# Circuito_Alarma.net
KiCad netlist of a schematic drawn in EAGLE
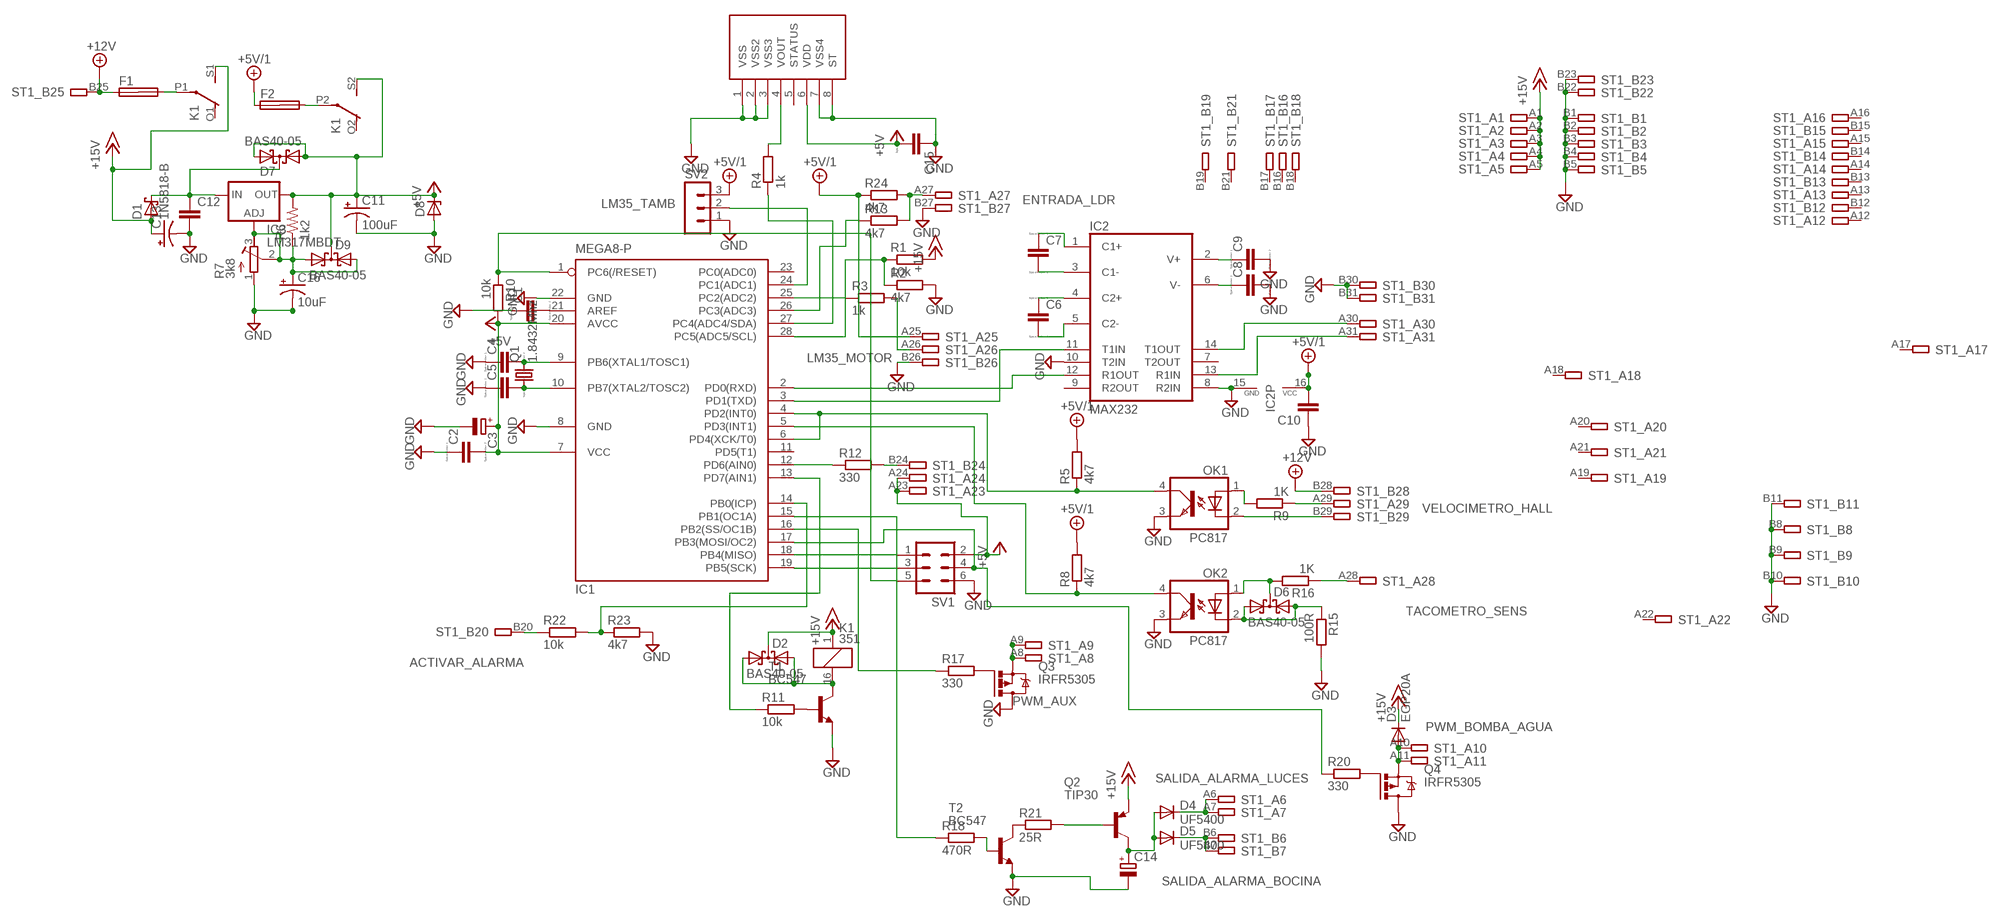
[diagram p0: schematic, sheet 1]

(export (version "E")
  (design (tool "Eeschema 10.0.6"))
  (components
    (comp (ref "C1")
      (value "CC1206")
      (footprint "eagle-import:C1206")
      (libsource (lib "eagle-import") (part "CC1206"))
    )
    (comp (ref "C2")
      (value "CC1206")
      (footprint "eagle-import:C1206")
      (libsource (lib "eagle-import") (part "CC1206"))
    )
    (comp (ref "C3")
      (value "CPOL-EUE2.5-5")
      (footprint "eagle-import:E2,5-5")
      (libsource (lib "eagle-import") (part "CPOL-EUE2.5-5"))
    )
    (comp (ref "C4")
      (value "CC1206")
      (footprint "eagle-import:C1206")
      (libsource (lib "eagle-import") (part "CC1206"))
    )
    (comp (ref "C5")
      (value "CC1206")
      (footprint "eagle-import:C1206")
      (libsource (lib "eagle-import") (part "CC1206"))
    )
    (comp (ref "C6")
      (value "CC1206")
      (footprint "eagle-import:C1206")
      (libsource (lib "eagle-import") (part "CC1206"))
    )
    (comp (ref "C7")
      (value "CC1206")
      (footprint "eagle-import:C1206")
      (libsource (lib "eagle-import") (part "CC1206"))
    )
    (comp (ref "C8")
      (value "CC1206")
      (footprint "eagle-import:C1206")
      (libsource (lib "eagle-import") (part "CC1206"))
    )
    (comp (ref "C9")
      (value "CC1206")
      (footprint "eagle-import:C1206")
      (libsource (lib "eagle-import") (part "CC1206"))
    )
    (comp (ref "C10")
      (value "C-EU050-024X044")
      (footprint "eagle-import:C050-024X044")
      (libsource (lib "eagle-import") (part "C-EU050-024X044"))
    )
    (comp (ref "C11")
      (value "100uF")
      (footprint "eagle-import:E2,5-5")
      (libsource (lib "eagle-import") (part "CPOL-USE2.5-5"))
    )
    (comp (ref "C12")
      (value "C-EU050-024X044")
      (footprint "eagle-import:C050-024X044")
      (libsource (lib "eagle-import") (part "C-EU050-024X044"))
    )
    (comp (ref "C13")
      (value "CPOL-USE2.5-5")
      (footprint "eagle-import:E2,5-5")
      (libsource (lib "eagle-import") (part "CPOL-USE2.5-5"))
    )
    (comp (ref "C14")
      (value "CPOL-EUE2.5-5")
      (footprint "eagle-import:E2,5-5")
      (libsource (lib "eagle-import") (part "CPOL-EUE2.5-5"))
    )
    (comp (ref "C15")
      (value "CC1206")
      (footprint "eagle-import:C1206")
      (libsource (lib "eagle-import") (part "CC1206"))
    )
    (comp (ref "C16")
      (value "10uF")
      (footprint "eagle-import:E2,5-5")
      (libsource (lib "eagle-import") (part "CPOL-USE2.5-5"))
    )
    (comp (ref "D1")
      (value "1N5818-B")
      (footprint "eagle-import:DO41-7.6")
      (libsource (lib "eagle-import") (part "1N5818-B"))
    )
    (comp (ref "D2")
      (value "BAS40-05")
      (footprint "eagle-import:SOT23")
      (libsource (lib "eagle-import") (part "BAS40-05"))
    )
    (comp (ref "D3")
      (value "EGP20A")
      (footprint "eagle-import:DO15-12")
      (libsource (lib "eagle-import") (part "EGP20A"))
    )
    (comp (ref "D4")
      (value "UF5400")
      (footprint "eagle-import:DO201-15")
      (libsource (lib "eagle-import") (part "UF5400"))
    )
    (comp (ref "D5")
      (value "UF5400")
      (footprint "eagle-import:DO201-15")
      (libsource (lib "eagle-import") (part "UF5400"))
    )
    (comp (ref "D6")
      (value "BAS40-05")
      (footprint "eagle-import:SOT23")
      (libsource (lib "eagle-import") (part "BAS40-05"))
    )
    (comp (ref "D7")
      (value "BAS40-05")
      (footprint "eagle-import:SOT23")
      (libsource (lib "eagle-import") (part "BAS40-05"))
    )
    (comp (ref "D8")
      (value "ZENER-DIODEZD-5")
      (footprint "eagle-import:ZDIO-5")
      (libsource (lib "eagle-import") (part "ZENER-DIODEZD-5"))
    )
    (comp (ref "D9")
      (value "BAS40-05")
      (footprint "eagle-import:SOT23")
      (libsource (lib "eagle-import") (part "BAS40-05"))
    )
    (comp (ref "F1")
      (value "SHK20L")
      (footprint "eagle-import:SHK20L")
      (libsource (lib "eagle-import") (part "SHK20L"))
    )
    (comp (ref "F2")
      (value "SHK20L")
      (footprint "eagle-import:SHK20L")
      (libsource (lib "eagle-import") (part "SHK20L"))
    )
    (comp (ref "IC1")
      (value "MEGA8-P")
      (footprint "eagle-import:DIL28-3")
      (libsource (lib "eagle-import") (part "MEGA8-P"))
    )
    (comp (ref "IC2")
      (value "MAX232")
      (footprint "eagle-import:DIL16")
      (fields (field (name "MF") "MAXIM") (field (name "MPN") "MAX232ACPE+"))
      (libsource (lib "eagle-import") (part "MAX232"))
    )
    (comp (ref "IC3")
      (value "LM317MBDT")
      (footprint "eagle-import:DPACK")
      (libsource (lib "eagle-import") (part "LM317?MBDT"))
    )
    (comp (ref "K1")
      (value "351")
      (footprint "eagle-import:351")
      (libsource (lib "eagle-import") (part "351"))
    )
    (comp (ref "OK1")
      (value "PC817")
      (footprint "eagle-import:DIL04")
      (fields (field (name "MPN") "PC817X4J000F"))
      (libsource (lib "eagle-import") (part "PC817"))
    )
    (comp (ref "OK2")
      (value "PC817")
      (footprint "eagle-import:DIL04")
      (fields (field (name "MPN") "PC817X4J000F"))
      (libsource (lib "eagle-import") (part "PC817"))
    )
    (comp (ref "Q1")
      (value "1.8432Mhz")
      (footprint "eagle-import:TC26H")
      (libsource (lib "eagle-import") (part "CRYSTALTC26H"))
    )
    (comp (ref "Q2")
      (value "TIP30")
      (footprint "eagle-import:TO220")
      (libsource (lib "eagle-import") (part "TIP30"))
    )
    (comp (ref "Q3")
      (value "IRFR5305")
      (footprint "eagle-import:D-PAK_TO252AA")
      (libsource (lib "eagle-import") (part "IRF?5305R"))
    )
    (comp (ref "Q4")
      (value "IRFR5305")
      (footprint "eagle-import:D-PAK_TO252AA")
      (libsource (lib "eagle-import") (part "IRF?5305R"))
    )
    (comp (ref "R1")
      (value "10k")
      (footprint "eagle-import:0204_5")
      (libsource (lib "eagle-import") (part "R-EU_0204/5"))
    )
    (comp (ref "R2")
      (value "4k7")
      (footprint "eagle-import:0204_5")
      (libsource (lib "eagle-import") (part "R-EU_0204/5"))
    )
    (comp (ref "R3")
      (value "1k")
      (footprint "eagle-import:0204_5")
      (libsource (lib "eagle-import") (part "R-EU_0204/5"))
    )
    (comp (ref "R4")
      (value "1k")
      (footprint "eagle-import:0204_5")
      (libsource (lib "eagle-import") (part "R-EU_0204/5"))
    )
    (comp (ref "R5")
      (value "4k7")
      (footprint "eagle-import:0204_5")
      (libsource (lib "eagle-import") (part "R-EU_0204/5"))
    )
    (comp (ref "R6")
      (value "1k2")
      (footprint "eagle-import:M1206")
      (libsource (lib "eagle-import") (part "R-US_M1206"))
    )
    (comp (ref "R7")
      (value "3k8")
      (footprint "eagle-import:RTRIM64W")
      (libsource (lib "eagle-import") (part "R-TRIMM64W"))
    )
    (comp (ref "R8")
      (value "4k7")
      (footprint "eagle-import:0204_5")
      (libsource (lib "eagle-import") (part "R-EU_0204/5"))
    )
    (comp (ref "R9")
      (value "1K")
      (footprint "eagle-import:0204_5")
      (libsource (lib "eagle-import") (part "R-EU_0204/5"))
    )
    (comp (ref "R10")
      (value "10k")
      (footprint "eagle-import:0204_5")
      (libsource (lib "eagle-import") (part "R-EU_0204/5"))
    )
    (comp (ref "R11")
      (value "10k")
      (footprint "eagle-import:0204_5")
      (libsource (lib "eagle-import") (part "R-EU_0204/5"))
    )
    (comp (ref "R12")
      (value "330")
      (footprint "eagle-import:0204_5")
      (libsource (lib "eagle-import") (part "R-EU_0204/5"))
    )
    (comp (ref "R13")
      (value "4k7")
      (footprint "eagle-import:0204_5")
      (libsource (lib "eagle-import") (part "R-EU_0204/5"))
    )
    (comp (ref "R15")
      (value "100R")
      (footprint "eagle-import:0204_5")
      (libsource (lib "eagle-import") (part "R-EU_0204/5"))
    )
    (comp (ref "R16")
      (value "1K")
      (footprint "eagle-import:0204_5")
      (libsource (lib "eagle-import") (part "R-EU_0204/5"))
    )
    (comp (ref "R17")
      (value "330")
      (footprint "eagle-import:0204_5")
      (libsource (lib "eagle-import") (part "R-EU_0204/5"))
    )
    (comp (ref "R18")
      (value "470R")
      (footprint "eagle-import:0204_5")
      (libsource (lib "eagle-import") (part "R-EU_0204/5"))
    )
    (comp (ref "R20")
      (value "330")
      (footprint "eagle-import:0204_5")
      (libsource (lib "eagle-import") (part "R-EU_0204/5"))
    )
    (comp (ref "R21")
      (value "25R")
      (footprint "eagle-import:0411_12")
      (libsource (lib "eagle-import") (part "R-EU_0411/12"))
    )
    (comp (ref "R22")
      (value "10k")
      (footprint "eagle-import:0204_5")
      (libsource (lib "eagle-import") (part "R-EU_0204/5"))
    )
    (comp (ref "R23")
      (value "4k7")
      (footprint "eagle-import:0204_5")
      (libsource (lib "eagle-import") (part "R-EU_0204/5"))
    )
    (comp (ref "R24")
      (value "4k7")
      (footprint "eagle-import:0204_5")
      (libsource (lib "eagle-import") (part "R-EU_0204/5"))
    )
    (comp (ref "ST1")
      (value "IBM8BIT")
      (footprint "eagle-import:IBM8BIT")
      (libsource (lib "eagle-import") (part "IBM8BIT"))
    )
    (comp (ref "SV1")
      (value "MA03-2")
      (footprint "eagle-import:MA03-2")
      (libsource (lib "eagle-import") (part "MA03-2"))
    )
    (comp (ref "SV2")
      (value "MA03-1")
      (footprint "eagle-import:MA03-1")
      (libsource (lib "eagle-import") (part "MA03-1"))
    )
    (comp (ref "T1")
      (value "BC547")
      (footprint "eagle-import:TO92")
      (libsource (lib "eagle-import") (part "BC547"))
    )
    (comp (ref "T2")
      (value "BC547")
      (footprint "eagle-import:TO92")
      (libsource (lib "eagle-import") (part "BC547"))
    )
    (comp (ref "U$1")
      (value "MMA1260")
      (footprint "eagle-import:N5")
      (libsource (lib "eagle-import") (part "MMA1260"))
    )
  )
  (nets
    (net (code "1") (name "+5V") (class "Default")
      (node (ref "C11") (pin "+") (pinfunction "+_+") (pintype "passive"))
      (node (ref "C15") (pin "2") (pinfunction "2_2") (pintype "passive"))
      (node (ref "C2") (pin "2") (pinfunction "2_2") (pintype "passive"))
      (node (ref "C3") (pin "+") (pinfunction "+_+") (pintype "passive"))
      (node (ref "D7") (pin "1") (pinfunction "A1_1") (pintype "passive"))
      (node (ref "D7") (pin "2") (pinfunction "A2_2") (pintype "passive"))
      (node (ref "D8") (pin "C") (pinfunction "C_C") (pintype "passive"))
      (node (ref "D9") (pin "3") (pinfunction "C_3") (pintype "passive"))
      (node (ref "IC1") (pin "20") (pinfunction "AVCC_20") (pintype "power_in"))
      (node (ref "IC1") (pin "7") (pinfunction "VCC_7") (pintype "power_in"))
      (node (ref "IC3") (pin "4") (pinfunction "OUT_4") (pintype "passive"))
      (node (ref "K1") (pin "S2") (pinfunction "S_S2") (pintype "passive"))
      (node (ref "R10") (pin "2") (pinfunction "2_2") (pintype "passive"))
      (node (ref "R6") (pin "2") (pinfunction "2_2") (pintype "passive"))
      (node (ref "ST1") (pin "A23") (pinfunction "P_A23") (pintype "bidirectional"))
      (node (ref "ST1") (pin "A24") (pinfunction "P_A24") (pintype "bidirectional"))
      (node (ref "SV1") (pin "2") (pinfunction "2_2") (pintype "passive"))
      (node (ref "U$1") (pin "6") (pinfunction "VDD_6") (pintype "bidirectional"))
    )
    (net (code "2") (name "+5V{slash}1") (class "Default")
      (node (ref "C10") (pin "2") (pinfunction "2_2") (pintype "passive"))
      (node (ref "F2") (pin "1A") (pinfunction "1A_1A") (pintype "passive"))
      (node (ref "IC2") (pin "16") (pinfunction "VCC_16") (pintype "power_in"))
      (node (ref "R24") (pin "1") (pinfunction "1_1") (pintype "passive"))
      (node (ref "R5") (pin "2") (pinfunction "2_2") (pintype "passive"))
      (node (ref "R8") (pin "2") (pinfunction "2_2") (pintype "passive"))
      (node (ref "ST1") (pin "A25") (pinfunction "P_A25") (pintype "bidirectional"))
      (node (ref "SV2") (pin "3") (pinfunction "3_3") (pintype "passive"))
    )
    (net (code "3") (name "+12V") (class "Default")
      (node (ref "F1") (pin "1A") (pinfunction "1A_1A") (pintype "passive"))
      (node (ref "ST1") (pin "B25") (pinfunction "P_B25") (pintype "bidirectional"))
      (node (ref "ST1") (pin "B28") (pinfunction "P_B28") (pintype "bidirectional"))
    )
    (net (code "4") (name "+15V") (class "Default")
      (node (ref "C13") (pin "+") (pinfunction "+_+") (pintype "passive"))
      (node (ref "D1") (pin "A") (pinfunction "A_A") (pintype "passive"))
      (node (ref "D2") (pin "3") (pinfunction "C_3") (pintype "passive"))
      (node (ref "D3") (pin "C") (pinfunction "C_C") (pintype "passive"))
      (node (ref "K1") (pin "1") (pinfunction "1_1") (pintype "passive"))
      (node (ref "K1") (pin "S1") (pinfunction "S_S1") (pintype "passive"))
      (node (ref "Q2") (pin "3") (pinfunction "E_3") (pintype "passive"))
      (node (ref "R1") (pin "2") (pinfunction "2_2") (pintype "passive"))
      (node (ref "ST1") (pin "A1") (pinfunction "P_A1") (pintype "bidirectional"))
      (node (ref "ST1") (pin "A2") (pinfunction "P_A2") (pintype "bidirectional"))
      (node (ref "ST1") (pin "A3") (pinfunction "P_A3") (pintype "bidirectional"))
      (node (ref "ST1") (pin "A4") (pinfunction "P_A4") (pintype "bidirectional"))
      (node (ref "ST1") (pin "A5") (pinfunction "P_A5") (pintype "bidirectional"))
    )
    (net (code "5") (name "/ACTIVAR_ALARMA") (class "Default")
      (node (ref "R22") (pin "1") (pinfunction "1_1") (pintype "passive"))
      (node (ref "ST1") (pin "B20") (pinfunction "P_B20") (pintype "bidirectional"))
    )
    (net (code "6") (name "/ENTRADA_LDR") (class "Default")
      (node (ref "R13") (pin "2") (pinfunction "2_2") (pintype "passive"))
      (node (ref "R24") (pin "2") (pinfunction "2_2") (pintype "passive"))
      (node (ref "ST1") (pin "A27") (pinfunction "P_A27") (pintype "bidirectional"))
    )
    (net (code "7") (name "/LM35_MOTOR") (class "Default")
      (node (ref "R3") (pin "2") (pinfunction "2_2") (pintype "passive"))
      (node (ref "ST1") (pin "A26") (pinfunction "P_A26") (pintype "bidirectional"))
    )
    (net (code "8") (name "/LM35_TAMB") (class "Default")
      (node (ref "IC1") (pin "24") (pinfunction "PC1(ADC1)_24") (pintype "bidirectional"))
      (node (ref "SV2") (pin "2") (pinfunction "2_2") (pintype "passive"))
    )
    (net (code "9") (name "/PWM_AUX") (class "Default")
      (node (ref "Q3") (pin "3") (pinfunction "S_3") (pintype "passive"))
      (node (ref "ST1") (pin "A8") (pinfunction "P_A8") (pintype "bidirectional"))
      (node (ref "ST1") (pin "A9") (pinfunction "P_A9") (pintype "bidirectional"))
    )
    (net (code "10") (name "/PWM_BOMBA_AGUA") (class "Default")
      (node (ref "D3") (pin "A") (pinfunction "A_A") (pintype "passive"))
      (node (ref "Q4") (pin "3") (pinfunction "S_3") (pintype "passive"))
      (node (ref "ST1") (pin "A10") (pinfunction "P_A10") (pintype "bidirectional"))
      (node (ref "ST1") (pin "A11") (pinfunction "P_A11") (pintype "bidirectional"))
    )
    (net (code "11") (name "/SALIDA_ALARMA_BOCINA") (class "Default")
      (node (ref "D5") (pin "C") (pinfunction "C_C") (pintype "passive"))
      (node (ref "ST1") (pin "B6") (pinfunction "P_B6") (pintype "bidirectional"))
      (node (ref "ST1") (pin "B7") (pinfunction "P_B7") (pintype "bidirectional"))
    )
    (net (code "12") (name "/SALIDA_ALARMA_LUCES") (class "Default")
      (node (ref "D4") (pin "C") (pinfunction "C_C") (pintype "passive"))
      (node (ref "ST1") (pin "A6") (pinfunction "P_A6") (pintype "bidirectional"))
      (node (ref "ST1") (pin "A7") (pinfunction "P_A7") (pintype "bidirectional"))
    )
    (net (code "13") (name "/TACOMETRO_SENS") (class "Default")
      (node (ref "D6") (pin "1") (pinfunction "A1_1") (pintype "passive"))
      (node (ref "D6") (pin "2") (pinfunction "A2_2") (pintype "passive"))
      (node (ref "OK2") (pin "2") (pinfunction "C_2") (pintype "passive"))
      (node (ref "R15") (pin "1") (pinfunction "1_1") (pintype "passive"))
    )
    (net (code "14") (name "/VELOCIMETRO_HALL") (class "Default")
      (node (ref "OK1") (pin "2") (pinfunction "C_2") (pintype "passive"))
      (node (ref "ST1") (pin "B29") (pinfunction "P_B29") (pintype "bidirectional"))
    )
    (net (code "15") (name "GND") (class "Default")
      (node (ref "C1") (pin "1") (pinfunction "1_1") (pintype "passive"))
      (node (ref "C10") (pin "1") (pinfunction "1_1") (pintype "passive"))
      (node (ref "C11") (pin "-") (pinfunction "-_-") (pintype "passive"))
      (node (ref "C12") (pin "2") (pinfunction "2_2") (pintype "passive"))
      (node (ref "C13") (pin "-") (pinfunction "-_-") (pintype "passive"))
      (node (ref "C14") (pin "-") (pinfunction "-_-") (pintype "passive"))
      (node (ref "C15") (pin "1") (pinfunction "1_1") (pintype "passive"))
      (node (ref "C16") (pin "-") (pinfunction "-_-") (pintype "passive"))
      (node (ref "C2") (pin "1") (pinfunction "1_1") (pintype "passive"))
      (node (ref "C3") (pin "-") (pinfunction "-_-") (pintype "passive"))
      (node (ref "C4") (pin "1") (pinfunction "1_1") (pintype "passive"))
      (node (ref "C5") (pin "1") (pinfunction "1_1") (pintype "passive"))
      (node (ref "C8") (pin "2") (pinfunction "2_2") (pintype "passive"))
      (node (ref "C9") (pin "2") (pinfunction "2_2") (pintype "passive"))
      (node (ref "D8") (pin "A") (pinfunction "A_A") (pintype "passive"))
      (node (ref "IC1") (pin "22") (pinfunction "GND_22") (pintype "power_in"))
      (node (ref "IC1") (pin "8") (pinfunction "GND_8") (pintype "power_in"))
      (node (ref "IC2") (pin "10") (pinfunction "T2IN_10") (pintype "input"))
      (node (ref "IC2") (pin "15") (pinfunction "GND_15") (pintype "power_in"))
      (node (ref "IC2") (pin "8") (pinfunction "R2IN_8") (pintype "input"))
      (node (ref "OK1") (pin "3") (pinfunction "EMIT_3") (pintype "passive"))
      (node (ref "OK2") (pin "3") (pinfunction "EMIT_3") (pintype "passive"))
      (node (ref "Q3") (pin "4") (pinfunction "D_4") (pintype "passive"))
      (node (ref "Q4") (pin "4") (pinfunction "D_4") (pintype "passive"))
      (node (ref "R15") (pin "2") (pinfunction "2_2") (pintype "passive"))
      (node (ref "R2") (pin "2") (pinfunction "2_2") (pintype "passive"))
      (node (ref "R23") (pin "2") (pinfunction "2_2") (pintype "passive"))
      (node (ref "R7") (pin "1") (pinfunction "E_1") (pintype "passive"))
      (node (ref "ST1") (pin "B1") (pinfunction "P_B1") (pintype "bidirectional"))
      (node (ref "ST1") (pin "B10") (pinfunction "P_B10") (pintype "bidirectional"))
      (node (ref "ST1") (pin "B11") (pinfunction "P_B11") (pintype "bidirectional"))
      (node (ref "ST1") (pin "B2") (pinfunction "P_B2") (pintype "bidirectional"))
      (node (ref "ST1") (pin "B22") (pinfunction "P_B22") (pintype "bidirectional"))
      (node (ref "ST1") (pin "B23") (pinfunction "P_B23") (pintype "bidirectional"))
      (node (ref "ST1") (pin "B26") (pinfunction "P_B26") (pintype "bidirectional"))
      (node (ref "ST1") (pin "B27") (pinfunction "P_B27") (pintype "bidirectional"))
      (node (ref "ST1") (pin "B3") (pinfunction "P_B3") (pintype "bidirectional"))
      (node (ref "ST1") (pin "B30") (pinfunction "P_B30") (pintype "bidirectional"))
      (node (ref "ST1") (pin "B31") (pinfunction "P_B31") (pintype "bidirectional"))
      (node (ref "ST1") (pin "B4") (pinfunction "P_B4") (pintype "bidirectional"))
      (node (ref "ST1") (pin "B5") (pinfunction "P_B5") (pintype "bidirectional"))
      (node (ref "ST1") (pin "B8") (pinfunction "P_B8") (pintype "bidirectional"))
      (node (ref "ST1") (pin "B9") (pinfunction "P_B9") (pintype "bidirectional"))
      (node (ref "SV1") (pin "6") (pinfunction "6_6") (pintype "passive"))
      (node (ref "SV2") (pin "1") (pinfunction "1_1") (pintype "passive"))
      (node (ref "T1") (pin "1") (pinfunction "E_1") (pintype "passive"))
      (node (ref "T2") (pin "1") (pinfunction "E_1") (pintype "passive"))
      (node (ref "U$1") (pin "1") (pinfunction "VSS_1") (pintype "bidirectional"))
      (node (ref "U$1") (pin "2") (pinfunction "VSS2_2") (pintype "bidirectional"))
      (node (ref "U$1") (pin "3") (pinfunction "VSS3_3") (pintype "bidirectional"))
      (node (ref "U$1") (pin "7") (pinfunction "VSS4_7") (pintype "bidirectional"))
      (node (ref "U$1") (pin "8") (pinfunction "ST_8") (pintype "bidirectional"))
    )
    (net (code "16") (name "Net-(D2-A1)") (class "Default")
      (node (ref "D2") (pin "1") (pinfunction "A1_1") (pintype "passive"))
      (node (ref "D2") (pin "2") (pinfunction "A2_2") (pintype "passive"))
      (node (ref "K1") (pin "16") (pinfunction "2_16") (pintype "passive"))
      (node (ref "T1") (pin "3") (pinfunction "C_3") (pintype "passive"))
    )
    (net (code "17") (name "Net-(D6-C)") (class "Default")
      (node (ref "D6") (pin "3") (pinfunction "C_3") (pintype "passive"))
      (node (ref "OK2") (pin "1") (pinfunction "A_1") (pintype "passive"))
      (node (ref "R16") (pin "2") (pinfunction "2_2") (pintype "passive"))
    )
    (net (code "18") (name "Net-(D7-C)") (class "Default")
      (node (ref "C12") (pin "1") (pinfunction "1_1") (pintype "passive"))
      (node (ref "D1") (pin "C") (pinfunction "C_C") (pintype "passive"))
      (node (ref "D7") (pin "3") (pinfunction "C_3") (pintype "passive"))
      (node (ref "IC3") (pin "3") (pinfunction "IN_3") (pintype "input"))
    )
    (net (code "19") (name "Net-(D9-A1)") (class "Default")
      (node (ref "C16") (pin "+") (pinfunction "+_+") (pintype "passive"))
      (node (ref "D9") (pin "1") (pinfunction "A1_1") (pintype "passive"))
      (node (ref "D9") (pin "2") (pinfunction "A2_2") (pintype "passive"))
      (node (ref "IC3") (pin "1") (pinfunction "ADJ_1") (pintype "input"))
      (node (ref "R6") (pin "1") (pinfunction "1_1") (pintype "passive"))
      (node (ref "R7") (pin "2") (pinfunction "S_2") (pintype "passive"))
      (node (ref "R7") (pin "3") (pinfunction "A_3") (pintype "passive"))
    )
    (net (code "20") (name "Net-(IC1-AREF)") (class "Default")
      (node (ref "C1") (pin "2") (pinfunction "2_2") (pintype "passive"))
      (node (ref "IC1") (pin "21") (pinfunction "AREF_21") (pintype "passive"))
    )
    (net (code "21") (name "Net-(IC1-PB0(ICP))") (class "Default")
      (node (ref "IC1") (pin "14") (pinfunction "PB0(ICP)_14") (pintype "bidirectional"))
      (node (ref "R22") (pin "2") (pinfunction "2_2") (pintype "passive"))
      (node (ref "R23") (pin "1") (pinfunction "1_1") (pintype "passive"))
    )
    (net (code "22") (name "Net-(IC1-PB1(OC1A))") (class "Default")
      (node (ref "IC1") (pin "15") (pinfunction "PB1(OC1A)_15") (pintype "bidirectional"))
      (node (ref "R18") (pin "1") (pinfunction "1_1") (pintype "passive"))
    )
    (net (code "23") (name "Net-(IC1-PB2(SS{slash}OC1B))") (class "Default")
      (node (ref "IC1") (pin "16") (pinfunction "PB2(SS/OC1B)_16") (pintype "bidirectional"))
      (node (ref "R17") (pin "1") (pinfunction "1_1") (pintype "passive"))
    )
    (net (code "24") (name "Net-(IC1-PB3(MOSI{slash}OC2))") (class "Default")
      (node (ref "IC1") (pin "17") (pinfunction "PB3(MOSI/OC2)_17") (pintype "bidirectional"))
      (node (ref "R20") (pin "1") (pinfunction "1_1") (pintype "passive"))
      (node (ref "SV1") (pin "4") (pinfunction "4_4") (pintype "passive"))
    )
    (net (code "25") (name "Net-(IC1-PB4(MISO))") (class "Default")
      (node (ref "IC1") (pin "18") (pinfunction "PB4(MISO)_18") (pintype "bidirectional"))
      (node (ref "SV1") (pin "1") (pinfunction "1_1") (pintype "passive"))
    )
    (net (code "26") (name "Net-(IC1-PB5(SCK))") (class "Default")
      (node (ref "IC1") (pin "19") (pinfunction "PB5(SCK)_19") (pintype "bidirectional"))
      (node (ref "SV1") (pin "3") (pinfunction "3_3") (pintype "passive"))
    )
    (net (code "27") (name "Net-(IC1-PB6(XTAL1{slash}TOSC1))") (class "Default")
      (node (ref "C4") (pin "2") (pinfunction "2_2") (pintype "passive"))
      (node (ref "IC1") (pin "9") (pinfunction "PB6(XTAL1/TOSC1)_9") (pintype "bidirectional"))
      (node (ref "Q1") (pin "2") (pinfunction "2_2") (pintype "passive"))
    )
    (net (code "28") (name "Net-(IC1-PB7(XTAL2{slash}TOSC2))") (class "Default")
      (node (ref "C5") (pin "2") (pinfunction "2_2") (pintype "passive"))
      (node (ref "IC1") (pin "10") (pinfunction "PB7(XTAL2/TOSC2)_10") (pintype "bidirectional"))
      (node (ref "Q1") (pin "1") (pinfunction "1_1") (pintype "passive"))
    )
    (net (code "29") (name "Net-(IC1-PC2(ADC2))") (class "Default")
      (node (ref "IC1") (pin "25") (pinfunction "PC2(ADC2)_25") (pintype "bidirectional"))
      (node (ref "R3") (pin "1") (pinfunction "1_1") (pintype "passive"))
    )
    (net (code "30") (name "Net-(IC1-PC3(ADC3))") (class "Default")
      (node (ref "IC1") (pin "26") (pinfunction "PC3(ADC3)_26") (pintype "bidirectional"))
      (node (ref "R13") (pin "1") (pinfunction "1_1") (pintype "passive"))
    )
    (net (code "31") (name "Net-(IC1-PC4(ADC4{slash}SDA))") (class "Default")
      (node (ref "IC1") (pin "27") (pinfunction "PC4(ADC4/SDA)_27") (pintype "bidirectional"))
      (node (ref "R4") (pin "1") (pinfunction "1_1") (pintype "passive"))
    )
    (net (code "32") (name "Net-(IC1-PC5(ADC5{slash}SCL))") (class "Default")
      (node (ref "IC1") (pin "28") (pinfunction "PC5(ADC5/SCL)_28") (pintype "bidirectional"))
      (node (ref "R1") (pin "1") (pinfunction "1_1") (pintype "passive"))
      (node (ref "R2") (pin "1") (pinfunction "1_1") (pintype "passive"))
    )
    (net (code "33") (name "Net-(IC1-PC6({slash}RESET))") (class "Default")
      (node (ref "IC1") (pin "1") (pinfunction "PC6(/RESET)_1") (pintype "bidirectional"))
      (node (ref "R10") (pin "1") (pinfunction "1_1") (pintype "passive"))
      (node (ref "SV1") (pin "5") (pinfunction "5_5") (pintype "passive"))
    )
    (net (code "34") (name "Net-(IC1-PD0(RXD))") (class "Default")
      (node (ref "IC1") (pin "2") (pinfunction "PD0(RXD)_2") (pintype "bidirectional"))
      (node (ref "IC2") (pin "12") (pinfunction "R1OUT_12") (pintype "output"))
    )
    (net (code "35") (name "Net-(IC1-PD1(TXD))") (class "Default")
      (node (ref "IC1") (pin "3") (pinfunction "PD1(TXD)_3") (pintype "bidirectional"))
      (node (ref "IC2") (pin "11") (pinfunction "T1IN_11") (pintype "input"))
    )
    (net (code "36") (name "Net-(IC1-PD2(INT0))") (class "Default")
      (node (ref "IC1") (pin "4") (pinfunction "PD2(INT0)_4") (pintype "bidirectional"))
      (node (ref "IC1") (pin "6") (pinfunction "PD4(XCK/T0)_6") (pintype "bidirectional"))
      (node (ref "OK1") (pin "4") (pinfunction "COL_4") (pintype "passive"))
      (node (ref "R5") (pin "1") (pinfunction "1_1") (pintype "passive"))
    )
    (net (code "37") (name "Net-(IC1-PD3(INT1))") (class "Default")
      (node (ref "IC1") (pin "5") (pinfunction "PD3(INT1)_5") (pintype "bidirectional"))
      (node (ref "OK2") (pin "4") (pinfunction "COL_4") (pintype "passive"))
      (node (ref "R8") (pin "1") (pinfunction "1_1") (pintype "passive"))
    )
    (net (code "38") (name "Net-(IC1-PD6(AIN0))") (class "Default")
      (node (ref "IC1") (pin "12") (pinfunction "PD6(AIN0)_12") (pintype "bidirectional"))
      (node (ref "R12") (pin "1") (pinfunction "1_1") (pintype "passive"))
    )
    (net (code "39") (name "Net-(IC1-PD7(AIN1))") (class "Default")
      (node (ref "IC1") (pin "13") (pinfunction "PD7(AIN1)_13") (pintype "bidirectional"))
      (node (ref "R11") (pin "1") (pinfunction "1_1") (pintype "passive"))
    )
    (net (code "40") (name "Net-(IC2A-C1+)") (class "Default")
      (node (ref "C7") (pin "1") (pinfunction "1_1") (pintype "passive"))
      (node (ref "IC2") (pin "1") (pinfunction "C1+_1") (pintype "bidirectional"))
    )
    (net (code "41") (name "Net-(IC2A-C1-)") (class "Default")
      (node (ref "C7") (pin "2") (pinfunction "2_2") (pintype "passive"))
      (node (ref "IC2") (pin "3") (pinfunction "C1-_3") (pintype "bidirectional"))
    )
    (net (code "42") (name "Net-(IC2A-C2+)") (class "Default")
      (node (ref "C6") (pin "1") (pinfunction "1_1") (pintype "passive"))
      (node (ref "IC2") (pin "4") (pinfunction "C2+_4") (pintype "bidirectional"))
    )
    (net (code "43") (name "Net-(IC2A-C2-)") (class "Default")
      (node (ref "C6") (pin "2") (pinfunction "2_2") (pintype "passive"))
      (node (ref "IC2") (pin "5") (pinfunction "C2-_5") (pintype "bidirectional"))
    )
    (net (code "44") (name "Net-(IC2A-R1IN)") (class "Default")
      (node (ref "IC2") (pin "13") (pinfunction "R1IN_13") (pintype "input"))
      (node (ref "ST1") (pin "A31") (pinfunction "P_A31") (pintype "bidirectional"))
    )
    (net (code "45") (name "Net-(IC2A-T1OUT)") (class "Default")
      (node (ref "IC2") (pin "14") (pinfunction "T1OUT_14") (pintype "output"))
      (node (ref "ST1") (pin "A30") (pinfunction "P_A30") (pintype "bidirectional"))
    )
    (net (code "46") (name "Net-(IC2A-V+)") (class "Default")
      (node (ref "C9") (pin "1") (pinfunction "1_1") (pintype "passive"))
      (node (ref "IC2") (pin "2") (pinfunction "V+_2") (pintype "bidirectional"))
    )
    (net (code "47") (name "Net-(IC2A-V-)") (class "Default")
      (node (ref "C8") (pin "1") (pinfunction "1_1") (pintype "passive"))
      (node (ref "IC2") (pin "6") (pinfunction "V-_6") (pintype "bidirectional"))
    )
    (net (code "48") (name "Net-(K1B-P)") (class "Default")
      (node (ref "F1") (pin "2A") (pinfunction "2A_2A") (pintype "passive"))
      (node (ref "K1") (pin "P1") (pinfunction "P_P1") (pintype "passive"))
    )
    (net (code "49") (name "Net-(K1C-P)") (class "Default")
      (node (ref "F2") (pin "2A") (pinfunction "2A_2A") (pintype "passive"))
      (node (ref "K1") (pin "P2") (pinfunction "P_P2") (pintype "passive"))
    )
    (net (code "50") (name "Net-(OK1-A)") (class "Default")
      (node (ref "OK1") (pin "1") (pinfunction "A_1") (pintype "passive"))
      (node (ref "R9") (pin "2") (pinfunction "2_2") (pintype "passive"))
    )
    (net (code "51") (name "Net-(Q2-B)") (class "Default")
      (node (ref "Q2") (pin "1") (pinfunction "B_1") (pintype "passive"))
      (node (ref "R21") (pin "2") (pinfunction "2_2") (pintype "passive"))
    )
    (net (code "52") (name "Net-(Q2-C)") (class "Default")
      (node (ref "C14") (pin "+") (pinfunction "+_+") (pintype "passive"))
      (node (ref "D4") (pin "A") (pinfunction "A_A") (pintype "passive"))
      (node (ref "D5") (pin "A") (pinfunction "A_A") (pintype "passive"))
      (node (ref "Q2") (pin "2") (pinfunction "C_2") (pintype "passive"))
    )
    (net (code "53") (name "Net-(Q3-G)") (class "Default")
      (node (ref "Q3") (pin "1") (pinfunction "G_1") (pintype "passive"))
      (node (ref "R17") (pin "2") (pinfunction "2_2") (pintype "passive"))
    )
    (net (code "54") (name "Net-(Q4-G)") (class "Default")
      (node (ref "Q4") (pin "1") (pinfunction "G_1") (pintype "passive"))
      (node (ref "R20") (pin "2") (pinfunction "2_2") (pintype "passive"))
    )
    (net (code "55") (name "Net-(ST1AV-P)") (class "Default")
      (node (ref "R12") (pin "2") (pinfunction "2_2") (pintype "passive"))
      (node (ref "ST1") (pin "B24") (pinfunction "P_B24") (pintype "bidirectional"))
    )
    (net (code "56") (name "Net-(ST1U-P)") (class "Default")
      (node (ref "R16") (pin "1") (pinfunction "1_1") (pintype "passive"))
      (node (ref "ST1") (pin "A28") (pinfunction "P_A28") (pintype "bidirectional"))
    )
    (net (code "57") (name "Net-(ST1V-P)") (class "Default")
      (node (ref "R9") (pin "1") (pinfunction "1_1") (pintype "passive"))
      (node (ref "ST1") (pin "A29") (pinfunction "P_A29") (pintype "bidirectional"))
    )
    (net (code "58") (name "Net-(T1-B)") (class "Default")
      (node (ref "R11") (pin "2") (pinfunction "2_2") (pintype "passive"))
      (node (ref "T1") (pin "2") (pinfunction "B_2") (pintype "passive"))
    )
    (net (code "59") (name "Net-(T2-B)") (class "Default")
      (node (ref "R18") (pin "2") (pinfunction "2_2") (pintype "passive"))
      (node (ref "T2") (pin "2") (pinfunction "B_2") (pintype "passive"))
    )
    (net (code "60") (name "Net-(T2-C)") (class "Default")
      (node (ref "R21") (pin "1") (pinfunction "1_1") (pintype "passive"))
      (node (ref "T2") (pin "3") (pinfunction "C_3") (pintype "passive"))
    )
    (net (code "61") (name "Net-(U$1-VOUT)") (class "Default")
      (node (ref "R4") (pin "2") (pinfunction "2_2") (pintype "passive"))
      (node (ref "U$1") (pin "4") (pinfunction "VOUT_4") (pintype "bidirectional"))
    )
    (net (code "62") (name "unconnected-(F1-Pad1B)") (class "Default")
      (node (ref "F1") (pin "1B") (pinfunction "1B_1B") (pintype "passive"))
    )
    (net (code "63") (name "unconnected-(F1-Pad2B)") (class "Default")
      (node (ref "F1") (pin "2B") (pinfunction "2B_2B") (pintype "passive"))
    )
    (net (code "64") (name "unconnected-(F2-Pad1B)") (class "Default")
      (node (ref "F2") (pin "1B") (pinfunction "1B_1B") (pintype "passive"))
    )
    (net (code "65") (name "unconnected-(F2-Pad2B)") (class "Default")
      (node (ref "F2") (pin "2B") (pinfunction "2B_2B") (pintype "passive"))
    )
    (net (code "66") (name "unconnected-(IC1-PC0(ADC0)-Pad23)") (class "Default")
      (node (ref "IC1") (pin "23") (pinfunction "PC0(ADC0)_23") (pintype "bidirectional"))
    )
    (net (code "67") (name "unconnected-(IC1-PD5(T1)-Pad11)") (class "Default")
      (node (ref "IC1") (pin "11") (pinfunction "PD5(T1)_11") (pintype "bidirectional"))
    )
    (net (code "68") (name "unconnected-(IC2A-R2OUT-Pad9)") (class "Default")
      (node (ref "IC2") (pin "9") (pinfunction "R2OUT_9") (pintype "output"))
    )
    (net (code "69") (name "unconnected-(IC2A-T2OUT-Pad7)") (class "Default")
      (node (ref "IC2") (pin "7") (pinfunction "T2OUT_7") (pintype "output"))
    )
    (net (code "70") (name "unconnected-(K1B-O-PadO1)") (class "Default")
      (node (ref "K1") (pin "O1") (pinfunction "O_O1") (pintype "passive"))
    )
    (net (code "71") (name "unconnected-(K1C-O-PadO2)") (class "Default")
      (node (ref "K1") (pin "O2") (pinfunction "O_O2") (pintype "passive"))
    )
    (net (code "72") (name "unconnected-(ST1AI-P-PadB12)") (class "Default")
      (node (ref "ST1") (pin "B12") (pinfunction "P_B12") (pintype "bidirectional"))
    )
    (net (code "73") (name "unconnected-(ST1AJ-P-PadB13)") (class "Default")
      (node (ref "ST1") (pin "B13") (pinfunction "P_B13") (pintype "bidirectional"))
    )
    (net (code "74") (name "unconnected-(ST1AK-P-PadB14)") (class "Default")
      (node (ref "ST1") (pin "B14") (pinfunction "P_B14") (pintype "bidirectional"))
    )
    (net (code "75") (name "unconnected-(ST1AL-P-PadB15)") (class "Default")
      (node (ref "ST1") (pin "B15") (pinfunction "P_B15") (pintype "bidirectional"))
    )
    (net (code "76") (name "unconnected-(ST1AM-P-PadB16)") (class "Default")
      (node (ref "ST1") (pin "B16") (pinfunction "P_B16") (pintype "bidirectional"))
    )
    (net (code "77") (name "unconnected-(ST1AN-P-PadB17)") (class "Default")
      (node (ref "ST1") (pin "B17") (pinfunction "P_B17") (pintype "bidirectional"))
    )
    (net (code "78") (name "unconnected-(ST1AO-P-PadB18)") (class "Default")
      (node (ref "ST1") (pin "B18") (pinfunction "P_B18") (pintype "bidirectional"))
    )
    (net (code "79") (name "unconnected-(ST1AP-P-PadB19)") (class "Default")
      (node (ref "ST1") (pin "B19") (pinfunction "P_B19") (pintype "bidirectional"))
    )
    (net (code "80") (name "unconnected-(ST1AS-P-PadB21)") (class "Default")
      (node (ref "ST1") (pin "B21") (pinfunction "P_B21") (pintype "bidirectional"))
    )
    (net (code "81") (name "unconnected-(ST1D-P-PadA12)") (class "Default")
      (node (ref "ST1") (pin "A12") (pinfunction "P_A12") (pintype "bidirectional"))
    )
    (net (code "82") (name "unconnected-(ST1E-P-PadA13)") (class "Default")
      (node (ref "ST1") (pin "A13") (pinfunction "P_A13") (pintype "bidirectional"))
    )
    (net (code "83") (name "unconnected-(ST1F-P-PadA14)") (class "Default")
      (node (ref "ST1") (pin "A14") (pinfunction "P_A14") (pintype "bidirectional"))
    )
    (net (code "84") (name "unconnected-(ST1G-P-PadA15)") (class "Default")
      (node (ref "ST1") (pin "A15") (pinfunction "P_A15") (pintype "bidirectional"))
    )
    (net (code "85") (name "unconnected-(ST1H-P-PadA16)") (class "Default")
      (node (ref "ST1") (pin "A16") (pinfunction "P_A16") (pintype "bidirectional"))
    )
    (net (code "86") (name "unconnected-(ST1I-P-PadA17)") (class "Default")
      (node (ref "ST1") (pin "A17") (pinfunction "P_A17") (pintype "bidirectional"))
    )
    (net (code "87") (name "unconnected-(ST1J-P-PadA18)") (class "Default")
      (node (ref "ST1") (pin "A18") (pinfunction "P_A18") (pintype "bidirectional"))
    )
    (net (code "88") (name "unconnected-(ST1K-P-PadA19)") (class "Default")
      (node (ref "ST1") (pin "A19") (pinfunction "P_A19") (pintype "bidirectional"))
    )
    (net (code "89") (name "unconnected-(ST1M-P-PadA20)") (class "Default")
      (node (ref "ST1") (pin "A20") (pinfunction "P_A20") (pintype "bidirectional"))
    )
    (net (code "90") (name "unconnected-(ST1N-P-PadA21)") (class "Default")
      (node (ref "ST1") (pin "A21") (pinfunction "P_A21") (pintype "bidirectional"))
    )
    (net (code "91") (name "unconnected-(ST1O-P-PadA22)") (class "Default")
      (node (ref "ST1") (pin "A22") (pinfunction "P_A22") (pintype "bidirectional"))
    )
    (net (code "92") (name "unconnected-(U$1-STATUS-Pad5)") (class "Default")
      (node (ref "U$1") (pin "5") (pinfunction "STATUS_5") (pintype "bidirectional"))
    )
  )
)
